# DifferentialProbe.net
KiCad netlist of a schematic drawn in Altium Designer
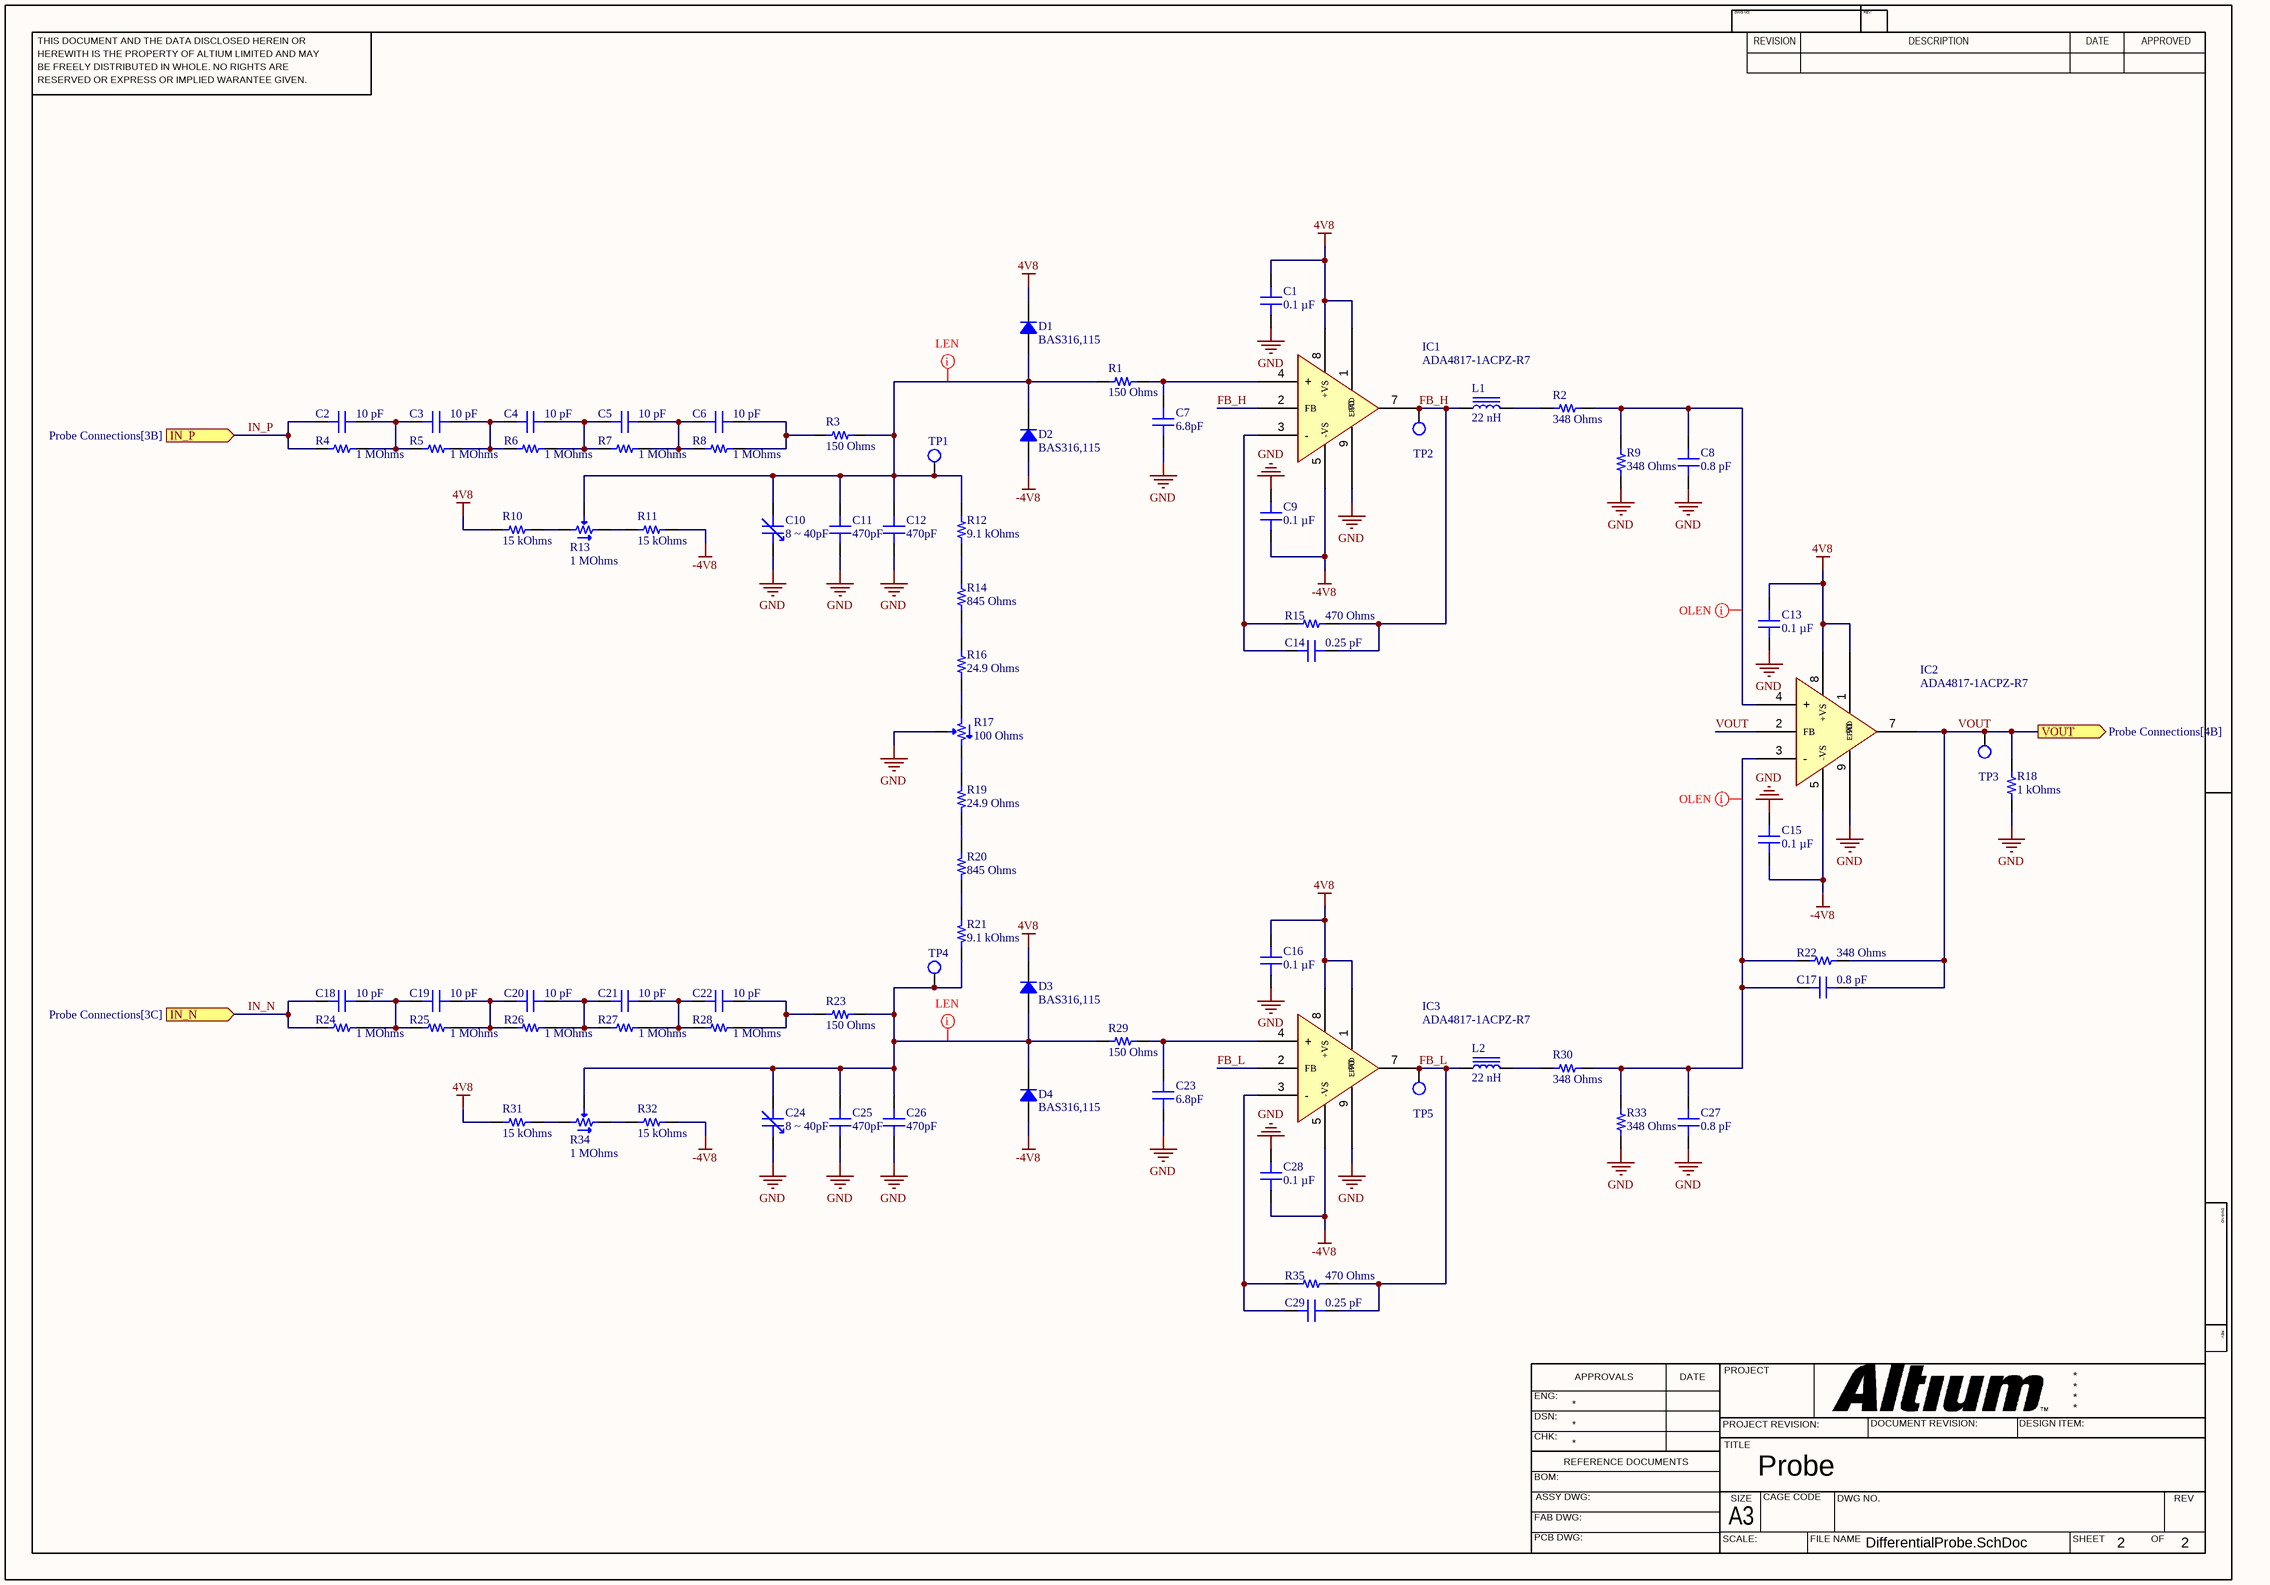
[diagram p0: DifferentialProbe.SchDoc]

(export (version "E")
  (design (tool "Eeschema 10.0.6"))
  (components
    (comp (ref "C1")
      (value "0.1 µF")
      (footprint "CAP 0402_1005")
      (description "CAP CER 0.1UF 10V X7R 0402")
      (fields
        (field (name "PART NUMBER") "0402B104K100CT")
        (field (name "MANUFACTURER") "Walsin Technology Corporation")
      )
      (libsource (lib "altiumlibrary.com") (part "Capacitor"))
    )
    (comp (ref "C2")
      (value "10 pF")
      (footprint "CAP 1206_3216 - 0.8MM")
      (description "CAP CER 10PF 500V C0G/NPO 1206")
      (fields (field (name "PART NUMBER") "CC1206JRNPOBBN100") (field (name "MANUFACTURER") "Yageo"))
      (libsource (lib "altiumlibrary.com") (part "Capacitor"))
    )
    (comp (ref "C3")
      (value "10 pF")
      (footprint "CAP 1206_3216 - 0.8MM")
      (description "CAP CER 10PF 500V C0G/NPO 1206")
      (fields (field (name "PART NUMBER") "CC1206JRNPOBBN100") (field (name "MANUFACTURER") "Yageo"))
      (libsource (lib "altiumlibrary.com") (part "Capacitor"))
    )
    (comp (ref "C4")
      (value "10 pF")
      (footprint "CAP 1206_3216 - 0.8MM")
      (description "CAP CER 10PF 500V C0G/NPO 1206")
      (fields (field (name "PART NUMBER") "CC1206JRNPOBBN100") (field (name "MANUFACTURER") "Yageo"))
      (libsource (lib "altiumlibrary.com") (part "Capacitor"))
    )
    (comp (ref "C5")
      (value "10 pF")
      (footprint "CAP 1206_3216 - 0.8MM")
      (description "CAP CER 10PF 500V C0G/NPO 1206")
      (fields (field (name "PART NUMBER") "CC1206JRNPOBBN100") (field (name "MANUFACTURER") "Yageo"))
      (libsource (lib "altiumlibrary.com") (part "Capacitor"))
    )
    (comp (ref "C6")
      (value "10 pF")
      (footprint "CAP 1206_3216 - 0.8MM")
      (description "CAP CER 10PF 500V C0G/NPO 1206")
      (fields (field (name "PART NUMBER") "CC1206JRNPOBBN100") (field (name "MANUFACTURER") "Yageo"))
      (libsource (lib "altiumlibrary.com") (part "Capacitor"))
    )
    (comp (ref "C7")
      (value "6.8pF")
      (footprint "CAP 0402_1005")
      (description "CAP CER 6.8PF 50V NP0 0402")
      (fields (field (name "PART NUMBER") "04025U6R8BAT2A") (field (name "MANUFACTURER") "AVX Corporation"))
      (libsource (lib "altiumlibrary.com") (part "Capacitor"))
    )
    (comp (ref "C8")
      (value "0.8 pF")
      (footprint "CAP 0402_1005")
      (description "CAP CER 0.8PF 50V C0G/NP0 0402")
      (fields (field (name "PART NUMBER") "CBR04C808C5GAC") (field (name "MANUFACTURER") "KEMET"))
      (libsource (lib "altiumlibrary.com") (part "Capacitor"))
    )
    (comp (ref "C9")
      (value "0.1 µF")
      (footprint "CAP 0402_1005")
      (description "CAP CER 0.1UF 10V X7R 0402")
      (fields
        (field (name "PART NUMBER") "0402B104K100CT")
        (field (name "MANUFACTURER") "Walsin Technology Corporation")
      )
      (libsource (lib "altiumlibrary.com") (part "Capacitor"))
    )
    (comp (ref "C10")
      (value "JZ400")
      (footprint "KNOWLES JZ")
      (description "CAP TRIMMER 8-40PF 125V SMD")
      (fields
        (field (name "CAPACITANCE RANGE") "8 ~ 40pF")
        (field (name "MANUFACTURER") "Knowles Voltronics")
      )
      (libsource (lib "altiumlibrary.com") (part "TRIMMER CAPACITOR"))
    )
    (comp (ref "C11")
      (value "470pF")
      (footprint "CAP 0402_1005")
      (description "CAP CER 470PF 50V C0G/NP0 0402")
      (fields (field (name "PART NUMBER") "04025A471JAT2A") (field (name "MANUFACTURER") "AVX Corporation"))
      (libsource (lib "altiumlibrary.com") (part "Capacitor"))
    )
    (comp (ref "C12")
      (value "470pF")
      (footprint "CAP 0402_1005")
      (description "CAP CER 470PF 50V C0G/NP0 0402")
      (fields (field (name "PART NUMBER") "04025A471JAT2A") (field (name "MANUFACTURER") "AVX Corporation"))
      (libsource (lib "altiumlibrary.com") (part "Capacitor"))
    )
    (comp (ref "C13")
      (value "0.1 µF")
      (footprint "CAP 0402_1005")
      (description "CAP CER 0.1UF 10V X7R 0402")
      (fields
        (field (name "PART NUMBER") "0402B104K100CT")
        (field (name "MANUFACTURER") "Walsin Technology Corporation")
      )
      (libsource (lib "altiumlibrary.com") (part "Capacitor"))
    )
    (comp (ref "C14")
      (value "0.25 pF")
      (footprint "CAP 0402_1005")
      (description "CAP CER 0.25PF 50V C0G/NP0 0402")
      (fields
        (field (name "PART NUMBER") "GCQ1555C1HR25BB01D")
        (field (name "MANUFACTURER") "Murata Electronics")
      )
      (libsource (lib "altiumlibrary.com") (part "Capacitor"))
    )
    (comp (ref "C15")
      (value "0.1 µF")
      (footprint "CAP 0402_1005")
      (description "CAP CER 0.1UF 10V X7R 0402")
      (fields
        (field (name "PART NUMBER") "0402B104K100CT")
        (field (name "MANUFACTURER") "Walsin Technology Corporation")
      )
      (libsource (lib "altiumlibrary.com") (part "Capacitor"))
    )
    (comp (ref "C16")
      (value "0.1 µF")
      (footprint "CAP 0402_1005")
      (description "CAP CER 0.1UF 10V X7R 0402")
      (fields
        (field (name "PART NUMBER") "0402B104K100CT")
        (field (name "MANUFACTURER") "Walsin Technology Corporation")
      )
      (libsource (lib "altiumlibrary.com") (part "Capacitor"))
    )
    (comp (ref "C17")
      (value "0.8 pF")
      (footprint "CAP 0402_1005")
      (description "CAP CER 0.8PF 50V C0G/NPO 0402")
      (fields (field (name "PART NUMBER") "CC0402BRNPO9BNR80") (field (name "MANUFACTURER") "Yageo"))
      (libsource (lib "altiumlibrary.com") (part "Capacitor"))
    )
    (comp (ref "C18")
      (value "10 pF")
      (footprint "CAP 1206_3216 - 0.8MM")
      (description "CAP CER 10PF 500V C0G/NPO 1206")
      (fields (field (name "PART NUMBER") "CC1206JRNPOBBN100") (field (name "MANUFACTURER") "Yageo"))
      (libsource (lib "altiumlibrary.com") (part "Capacitor"))
    )
    (comp (ref "C19")
      (value "10 pF")
      (footprint "CAP 1206_3216 - 0.8MM")
      (description "CAP CER 10PF 500V C0G/NPO 1206")
      (fields (field (name "PART NUMBER") "CC1206JRNPOBBN100") (field (name "MANUFACTURER") "Yageo"))
      (libsource (lib "altiumlibrary.com") (part "Capacitor"))
    )
    (comp (ref "C20")
      (value "10 pF")
      (footprint "CAP 1206_3216 - 0.8MM")
      (description "CAP CER 10PF 500V C0G/NPO 1206")
      (fields (field (name "PART NUMBER") "CC1206JRNPOBBN100") (field (name "MANUFACTURER") "Yageo"))
      (libsource (lib "altiumlibrary.com") (part "Capacitor"))
    )
    (comp (ref "C21")
      (value "10 pF")
      (footprint "CAP 1206_3216 - 0.8MM")
      (description "CAP CER 10PF 500V C0G/NPO 1206")
      (fields (field (name "PART NUMBER") "CC1206JRNPOBBN100") (field (name "MANUFACTURER") "Yageo"))
      (libsource (lib "altiumlibrary.com") (part "Capacitor"))
    )
    (comp (ref "C22")
      (value "10 pF")
      (footprint "CAP 1206_3216 - 0.8MM")
      (description "CAP CER 10PF 500V C0G/NPO 1206")
      (fields (field (name "PART NUMBER") "CC1206JRNPOBBN100") (field (name "MANUFACTURER") "Yageo"))
      (libsource (lib "altiumlibrary.com") (part "Capacitor"))
    )
    (comp (ref "C23")
      (value "6.8pF")
      (footprint "CAP 0402_1005")
      (description "CAP CER 6.8PF 50V NP0 0402")
      (fields (field (name "PART NUMBER") "04025U6R8BAT2A") (field (name "MANUFACTURER") "AVX Corporation"))
      (libsource (lib "altiumlibrary.com") (part "Capacitor"))
    )
    (comp (ref "C24")
      (value "JZ400")
      (footprint "KNOWLES JZ")
      (description "CAP TRIMMER 8-40PF 125V SMD")
      (fields
        (field (name "CAPACITANCE RANGE") "8 ~ 40pF")
        (field (name "MANUFACTURER") "Knowles Voltronics")
      )
      (libsource (lib "altiumlibrary.com") (part "TRIMMER CAPACITOR"))
    )
    (comp (ref "C25")
      (value "470pF")
      (footprint "CAP 0402_1005")
      (description "CAP CER 470PF 50V C0G/NP0 0402")
      (fields (field (name "PART NUMBER") "04025A471JAT2A") (field (name "MANUFACTURER") "AVX Corporation"))
      (libsource (lib "altiumlibrary.com") (part "Capacitor"))
    )
    (comp (ref "C26")
      (value "470pF")
      (footprint "CAP 0402_1005")
      (description "CAP CER 470PF 50V C0G/NP0 0402")
      (fields (field (name "PART NUMBER") "04025A471JAT2A") (field (name "MANUFACTURER") "AVX Corporation"))
      (libsource (lib "altiumlibrary.com") (part "Capacitor"))
    )
    (comp (ref "C27")
      (value "0.8 pF")
      (footprint "CAP 0402_1005")
      (description "CAP CER 0.8PF 50V C0G/NP0 0402")
      (fields (field (name "PART NUMBER") "CBR04C808C5GAC") (field (name "MANUFACTURER") "KEMET"))
      (libsource (lib "altiumlibrary.com") (part "Capacitor"))
    )
    (comp (ref "C28")
      (value "0.1 µF")
      (footprint "CAP 0402_1005")
      (description "CAP CER 0.1UF 10V X7R 0402")
      (fields
        (field (name "PART NUMBER") "0402B104K100CT")
        (field (name "MANUFACTURER") "Walsin Technology Corporation")
      )
      (libsource (lib "altiumlibrary.com") (part "Capacitor"))
    )
    (comp (ref "C29")
      (value "0.25 pF")
      (footprint "CAP 0402_1005")
      (description "CAP CER 0.25PF 50V C0G/NP0 0402")
      (fields
        (field (name "PART NUMBER") "GCQ1555C1HR25BB01D")
        (field (name "MANUFACTURER") "Murata Electronics")
      )
      (libsource (lib "altiumlibrary.com") (part "Capacitor"))
    )
    (comp (ref "D1")
      (value "BAS316,115")
      (footprint "SOD323")
      (description "DIODE GEN PURP 100V 250MA SOD323")
      (fields (field (name "MANUFACTURER") "Nexperia USA Inc."))
      (libsource (lib "altiumlibrary.com") (part "Diode"))
    )
    (comp (ref "D2")
      (value "BAS316,115")
      (footprint "SOD323")
      (description "DIODE GEN PURP 100V 250MA SOD323")
      (fields (field (name "MANUFACTURER") "Nexperia USA Inc."))
      (libsource (lib "altiumlibrary.com") (part "Diode"))
    )
    (comp (ref "D3")
      (value "BAS316,115")
      (footprint "SOD323")
      (description "DIODE GEN PURP 100V 250MA SOD323")
      (fields (field (name "MANUFACTURER") "Nexperia USA Inc."))
      (libsource (lib "altiumlibrary.com") (part "Diode"))
    )
    (comp (ref "D4")
      (value "BAS316,115")
      (footprint "SOD323")
      (description "DIODE GEN PURP 100V 250MA SOD323")
      (fields (field (name "MANUFACTURER") "Nexperia USA Inc."))
      (libsource (lib "altiumlibrary.com") (part "Diode"))
    )
    (comp (ref "IC1")
      (value "ADA4817-1ACPZ-R7")
      (footprint "AD LFCSP-8 3x3MM CP-8-5")
      (description "IC OPAMP VFB 1 CIRCUIT 8LFCSP")
      (fields (field (name "MANUFACTURER") "Analog Devices Inc."))
      (libsource (lib "altiumlibrary.com") (part "ANALOG DEV ADA4817-1 LFCSP"))
    )
    (comp (ref "IC2")
      (value "ADA4817-1ACPZ-R7")
      (footprint "AD LFCSP-8 3x3MM CP-8-5")
      (description "IC OPAMP VFB 1 CIRCUIT 8LFCSP")
      (fields (field (name "MANUFACTURER") "Analog Devices Inc."))
      (libsource (lib "altiumlibrary.com") (part "ANALOG DEV ADA4817-1 LFCSP"))
    )
    (comp (ref "IC3")
      (value "ADA4817-1ACPZ-R7")
      (footprint "AD LFCSP-8 3x3MM CP-8-5")
      (description "IC OPAMP VFB 1 CIRCUIT 8LFCSP")
      (fields (field (name "MANUFACTURER") "Analog Devices Inc."))
      (libsource (lib "altiumlibrary.com") (part "ANALOG DEV ADA4817-1 LFCSP"))
    )
    (comp (ref "L1")
      (value "22 nH")
      (footprint "IND 0402_1005 RF WW")
      (description "FIXED IND 22NH 780MA 202MOHM SMD")
      (fields
        (field (name "PART NUMBER") "LQW15AN22NG80D")
        (field (name "MANUFACTURER") "Murata Electronics")
      )
      (libsource (lib "altiumlibrary.com") (part "Inductor"))
    )
    (comp (ref "L2")
      (value "22 nH")
      (footprint "IND 0402_1005 RF WW")
      (description "FIXED IND 22NH 780MA 202MOHM SMD")
      (fields
        (field (name "PART NUMBER") "LQW15AN22NG80D")
        (field (name "MANUFACTURER") "Murata Electronics")
      )
      (libsource (lib "altiumlibrary.com") (part "Inductor"))
    )
    (comp (ref "R1")
      (value "150 Ohms")
      (footprint "RES 0402_1005")
      (description "RES SMD 150 OHM 0.1% 1/16W 0402")
      (fields (field (name "PART NUMBER") "RG1005P-151-B-T5") (field (name "MANUFACTURER") "Susumu"))
      (libsource (lib "altiumlibrary.com") (part "Resistor"))
    )
    (comp (ref "R2")
      (value "348 Ohms")
      (footprint "RES 0402_1005")
      (description "RES SMD 348 OHM 0.1% 1/16W 0402")
      (fields (field (name "PART NUMBER") "RT0402BRD07348RL") (field (name "MANUFACTURER") "Yageo"))
      (libsource (lib "altiumlibrary.com") (part "Resistor"))
    )
    (comp (ref "R3")
      (value "150 Ohms")
      (footprint "RES 0402_1005")
      (description "RES SMD 150 OHM 0.1% 1/16W 0402")
      (fields (field (name "PART NUMBER") "RG1005P-151-B-T5") (field (name "MANUFACTURER") "Susumu"))
      (libsource (lib "altiumlibrary.com") (part "Resistor"))
    )
    (comp (ref "R4")
      (value "1 MOhms")
      (footprint "RES 1206_3216")
      (description "RES 1M OHM 0.1% 1/8W 1206")
      (fields
        (field (name "PART NUMBER") "RNCS1206BKE1M00")
        (field (name "MANUFACTURER") "Stackpole Electronics Inc")
      )
      (libsource (lib "altiumlibrary.com") (part "Resistor"))
    )
    (comp (ref "R5")
      (value "1 MOhms")
      (footprint "RES 1206_3216")
      (description "RES 1M OHM 0.1% 1/8W 1206")
      (fields
        (field (name "PART NUMBER") "RNCS1206BKE1M00")
        (field (name "MANUFACTURER") "Stackpole Electronics Inc")
      )
      (libsource (lib "altiumlibrary.com") (part "Resistor"))
    )
    (comp (ref "R6")
      (value "1 MOhms")
      (footprint "RES 1206_3216")
      (description "RES 1M OHM 0.1% 1/8W 1206")
      (fields
        (field (name "PART NUMBER") "RNCS1206BKE1M00")
        (field (name "MANUFACTURER") "Stackpole Electronics Inc")
      )
      (libsource (lib "altiumlibrary.com") (part "Resistor"))
    )
    (comp (ref "R7")
      (value "1 MOhms")
      (footprint "RES 1206_3216")
      (description "RES 1M OHM 0.1% 1/8W 1206")
      (fields
        (field (name "PART NUMBER") "RNCS1206BKE1M00")
        (field (name "MANUFACTURER") "Stackpole Electronics Inc")
      )
      (libsource (lib "altiumlibrary.com") (part "Resistor"))
    )
    (comp (ref "R8")
      (value "1 MOhms")
      (footprint "RES 1206_3216")
      (description "RES 1M OHM 0.1% 1/8W 1206")
      (fields
        (field (name "PART NUMBER") "RNCS1206BKE1M00")
        (field (name "MANUFACTURER") "Stackpole Electronics Inc")
      )
      (libsource (lib "altiumlibrary.com") (part "Resistor"))
    )
    (comp (ref "R9")
      (value "348 Ohms")
      (footprint "RES 0402_1005")
      (description "RES SMD 348 OHM 0.1% 1/16W 0402")
      (fields (field (name "PART NUMBER") "RT0402BRD07348RL") (field (name "MANUFACTURER") "Yageo"))
      (libsource (lib "altiumlibrary.com") (part "Resistor"))
    )
    (comp (ref "R10")
      (value "15 kOhms")
      (footprint "RES 0402_1005")
      (description "RES 15K OHM 0.1% 1/16W 0402")
      (fields
        (field (name "PART NUMBER") "RN73R1ETTP1502B25")
        (field (name "MANUFACTURER") "KOA Speer Electronics, Inc.")
      )
      (libsource (lib "altiumlibrary.com") (part "Resistor"))
    )
    (comp (ref "R11")
      (value "15 kOhms")
      (footprint "RES 0402_1005")
      (description "RES 15K OHM 0.1% 1/16W 0402")
      (fields
        (field (name "PART NUMBER") "RN73R1ETTP1502B25")
        (field (name "MANUFACTURER") "KOA Speer Electronics, Inc.")
      )
      (libsource (lib "altiumlibrary.com") (part "Resistor"))
    )
    (comp (ref "R12")
      (value "9.1 kOhms")
      (footprint "RES 0402_1005")
      (description "RES SMD 9.1K OHM 0.1% 1/16W 0402")
      (fields
        (field (name "PART NUMBER") "CPF0402B9K1E1")
        (field (name "MANUFACTURER") "TE Connectivity Passive Product")
      )
      (libsource (lib "altiumlibrary.com") (part "Resistor"))
    )
    (comp (ref "R13")
      (value "1 MOhms")
      (footprint "BOURNS TRIMPOT 3386P-1")
      (description "TRIMMER 1M OHM 0.5W PC PIN TOP")
      (fields (field (name "PART NUMBER") "3386P-1-105LF") (field (name "MANUFACTURER") "Bourns Inc."))
      (libsource (lib "altiumlibrary.com") (part "Potentiometer"))
    )
    (comp (ref "R14")
      (value "845 Ohms")
      (footprint "RES 0402_1005")
      (description "RES SMD 845 OHM 0.1% 1/16W 0402")
      (fields
        (field (name "PART NUMBER") "ERA-2AEB8450X")
        (field (name "MANUFACTURER") "Panasonic Electronic Components")
      )
      (libsource (lib "altiumlibrary.com") (part "Resistor"))
    )
    (comp (ref "R15")
      (value "470 Ohms")
      (footprint "RES 0402_1005")
      (description "RES SMD 470 OHM 0.1% 1/16W 0402")
      (fields (field (name "PART NUMBER") "RT0402BRD07470RL") (field (name "MANUFACTURER") "Yageo"))
      (libsource (lib "altiumlibrary.com") (part "Resistor"))
    )
    (comp (ref "R16")
      (value "24.9 Ohms")
      (footprint "RES 0402_1005")
      (description "RES SMD 24.9 OHM 0.1% 1/16W 0402")
      (fields (field (name "PART NUMBER") "RT0402BRD0724R9L") (field (name "MANUFACTURER") "Yageo"))
      (libsource (lib "altiumlibrary.com") (part "Resistor"))
    )
    (comp (ref "R17")
      (value "100 Ohms")
      (footprint "BOURNS TRIMPOT 3386P-1")
      (description "TRIMMER 100 OHM 0.5W PC PIN TOP")
      (fields (field (name "PART NUMBER") "3386P-1-101LF") (field (name "MANUFACTURER") "Bourns Inc."))
      (libsource (lib "altiumlibrary.com") (part "Potentiometer"))
    )
    (comp (ref "R18")
      (value "1 kOhms")
      (footprint "RES 0402_1005")
      (description "RES 1K OHM 1% 1/16W 0402")
      (fields
        (field (name "PART NUMBER") "RMCF0402FT1K00")
        (field (name "MANUFACTURER") "Stackpole Electronics Inc")
      )
      (libsource (lib "altiumlibrary.com") (part "Resistor"))
    )
    (comp (ref "R19")
      (value "24.9 Ohms")
      (footprint "RES 0402_1005")
      (description "RES SMD 24.9 OHM 0.1% 1/16W 0402")
      (fields (field (name "PART NUMBER") "RT0402BRD0724R9L") (field (name "MANUFACTURER") "Yageo"))
      (libsource (lib "altiumlibrary.com") (part "Resistor"))
    )
    (comp (ref "R20")
      (value "845 Ohms")
      (footprint "RES 0402_1005")
      (description "RES SMD 845 OHM 0.1% 1/16W 0402")
      (fields
        (field (name "PART NUMBER") "ERA-2AEB8450X")
        (field (name "MANUFACTURER") "Panasonic Electronic Components")
      )
      (libsource (lib "altiumlibrary.com") (part "Resistor"))
    )
    (comp (ref "R21")
      (value "9.1 kOhms")
      (footprint "RES 0402_1005")
      (description "RES SMD 9.1K OHM 0.1% 1/16W 0402")
      (fields
        (field (name "PART NUMBER") "CPF0402B9K1E1")
        (field (name "MANUFACTURER") "TE Connectivity Passive Product")
      )
      (libsource (lib "altiumlibrary.com") (part "Resistor"))
    )
    (comp (ref "R22")
      (value "348 Ohms")
      (footprint "RES 0402_1005")
      (description "RES SMD 348 OHM 0.1% 1/16W 0402")
      (fields (field (name "PART NUMBER") "RT0402BRD07348RL") (field (name "MANUFACTURER") "Yageo"))
      (libsource (lib "altiumlibrary.com") (part "Resistor"))
    )
    (comp (ref "R23")
      (value "150 Ohms")
      (footprint "RES 0402_1005")
      (description "RES SMD 150 OHM 0.1% 1/16W 0402")
      (fields (field (name "PART NUMBER") "RG1005P-151-B-T5") (field (name "MANUFACTURER") "Susumu"))
      (libsource (lib "altiumlibrary.com") (part "Resistor"))
    )
    (comp (ref "R24")
      (value "1 MOhms")
      (footprint "RES 1206_3216")
      (description "RES 1M OHM 0.1% 1/8W 1206")
      (fields
        (field (name "PART NUMBER") "RNCS1206BKE1M00")
        (field (name "MANUFACTURER") "Stackpole Electronics Inc")
      )
      (libsource (lib "altiumlibrary.com") (part "Resistor"))
    )
    (comp (ref "R25")
      (value "1 MOhms")
      (footprint "RES 1206_3216")
      (description "RES 1M OHM 0.1% 1/8W 1206")
      (fields
        (field (name "PART NUMBER") "RNCS1206BKE1M00")
        (field (name "MANUFACTURER") "Stackpole Electronics Inc")
      )
      (libsource (lib "altiumlibrary.com") (part "Resistor"))
    )
    (comp (ref "R26")
      (value "1 MOhms")
      (footprint "RES 1206_3216")
      (description "RES 1M OHM 0.1% 1/8W 1206")
      (fields
        (field (name "PART NUMBER") "RNCS1206BKE1M00")
        (field (name "MANUFACTURER") "Stackpole Electronics Inc")
      )
      (libsource (lib "altiumlibrary.com") (part "Resistor"))
    )
    (comp (ref "R27")
      (value "1 MOhms")
      (footprint "RES 1206_3216")
      (description "RES 1M OHM 0.1% 1/8W 1206")
      (fields
        (field (name "PART NUMBER") "RNCS1206BKE1M00")
        (field (name "MANUFACTURER") "Stackpole Electronics Inc")
      )
      (libsource (lib "altiumlibrary.com") (part "Resistor"))
    )
    (comp (ref "R28")
      (value "1 MOhms")
      (footprint "RES 1206_3216")
      (description "RES 1M OHM 0.1% 1/8W 1206")
      (fields
        (field (name "PART NUMBER") "RNCS1206BKE1M00")
        (field (name "MANUFACTURER") "Stackpole Electronics Inc")
      )
      (libsource (lib "altiumlibrary.com") (part "Resistor"))
    )
    (comp (ref "R29")
      (value "150 Ohms")
      (footprint "RES 0402_1005")
      (description "RES SMD 150 OHM 0.1% 1/16W 0402")
      (fields (field (name "PART NUMBER") "RG1005P-151-B-T5") (field (name "MANUFACTURER") "Susumu"))
      (libsource (lib "altiumlibrary.com") (part "Resistor"))
    )
    (comp (ref "R30")
      (value "348 Ohms")
      (footprint "RES 0402_1005")
      (description "RES SMD 348 OHM 0.1% 1/16W 0402")
      (fields (field (name "PART NUMBER") "RT0402BRD07348RL") (field (name "MANUFACTURER") "Yageo"))
      (libsource (lib "altiumlibrary.com") (part "Resistor"))
    )
    (comp (ref "R31")
      (value "15 kOhms")
      (footprint "RES 0402_1005")
      (description "RES 15K OHM 0.1% 1/16W 0402")
      (fields
        (field (name "PART NUMBER") "RN73R1ETTP1502B25")
        (field (name "MANUFACTURER") "KOA Speer Electronics, Inc.")
      )
      (libsource (lib "altiumlibrary.com") (part "Resistor"))
    )
    (comp (ref "R32")
      (value "15 kOhms")
      (footprint "RES 0402_1005")
      (description "RES 15K OHM 0.1% 1/16W 0402")
      (fields
        (field (name "PART NUMBER") "RN73R1ETTP1502B25")
        (field (name "MANUFACTURER") "KOA Speer Electronics, Inc.")
      )
      (libsource (lib "altiumlibrary.com") (part "Resistor"))
    )
    (comp (ref "R33")
      (value "348 Ohms")
      (footprint "RES 0402_1005")
      (description "RES SMD 348 OHM 0.1% 1/16W 0402")
      (fields (field (name "PART NUMBER") "RT0402BRD07348RL") (field (name "MANUFACTURER") "Yageo"))
      (libsource (lib "altiumlibrary.com") (part "Resistor"))
    )
    (comp (ref "R34")
      (value "1 MOhms")
      (footprint "BOURNS TRIMPOT 3386P-1")
      (description "TRIMMER 1M OHM 0.5W PC PIN TOP")
      (fields (field (name "PART NUMBER") "3386P-1-105LF") (field (name "MANUFACTURER") "Bourns Inc."))
      (libsource (lib "altiumlibrary.com") (part "Potentiometer"))
    )
    (comp (ref "R35")
      (value "470 Ohms")
      (footprint "RES 0402_1005")
      (description "RES SMD 470 OHM 0.1% 1/16W 0402")
      (fields (field (name "PART NUMBER") "RT0402BRD07470RL") (field (name "MANUFACTURER") "Yageo"))
      (libsource (lib "altiumlibrary.com") (part "Resistor"))
    )
    (comp (ref "TP1")
      (value "Test Point")
      (footprint "TestPoint-1.5mm")
      (libsource (lib "Original Circuit") (part "Test Point"))
    )
    (comp (ref "TP2")
      (value "Test Point")
      (footprint "TestPoint-1.5mm")
      (libsource (lib "Original Circuit") (part "Test Point"))
    )
    (comp (ref "TP3")
      (value "Test Point")
      (footprint "TestPoint-1.5mm")
      (libsource (lib "Original Circuit") (part "Test Point"))
    )
    (comp (ref "TP4")
      (value "Test Point")
      (footprint "TestPoint-1.5mm")
      (libsource (lib "Original Circuit") (part "Test Point"))
    )
    (comp (ref "TP5")
      (value "Test Point")
      (footprint "TestPoint-1.5mm")
      (libsource (lib "Original Circuit") (part "Test Point"))
    )
  )
  (nets
    (net (code "1") (name "-4V8") (class "Default")
      (node (ref "C15") (pin "1") (pinfunction "1_1") (pintype "passive"))
      (node (ref "C28") (pin "1") (pinfunction "1_1") (pintype "passive"))
      (node (ref "C9") (pin "1") (pinfunction "1_1") (pintype "passive"))
      (node (ref "D2") (pin "1") (pinfunction "1_1") (pintype "passive"))
      (node (ref "D4") (pin "1") (pinfunction "1_1") (pintype "passive"))
      (node (ref "IC1") (pin "5") (pinfunction "-VS_5") (pintype "passive"))
      (node (ref "IC2") (pin "5") (pinfunction "-VS_5") (pintype "passive"))
      (node (ref "IC3") (pin "5") (pinfunction "-VS_5") (pintype "passive"))
      (node (ref "R11") (pin "2") (pinfunction "2_2") (pintype "passive"))
      (node (ref "R32") (pin "2") (pinfunction "2_2") (pintype "passive"))
    )
    (net (code "2") (name "/FB_H") (class "Default")
      (node (ref "C14") (pin "2") (pinfunction "2_2") (pintype "passive"))
      (node (ref "IC1") (pin "2") (pinfunction "FB_2") (pintype "passive"))
      (node (ref "IC1") (pin "7") (pinfunction "OUT_7") (pintype "passive"))
      (node (ref "L1") (pin "1") (pinfunction "1_1") (pintype "passive"))
      (node (ref "R15") (pin "2") (pinfunction "2_2") (pintype "passive"))
      (node (ref "TP2") (pin "1") (pinfunction "TP_1") (pintype "passive"))
    )
    (net (code "3") (name "/FB_L") (class "Default")
      (node (ref "C29") (pin "2") (pinfunction "2_2") (pintype "passive"))
      (node (ref "IC3") (pin "2") (pinfunction "FB_2") (pintype "passive"))
      (node (ref "IC3") (pin "7") (pinfunction "OUT_7") (pintype "passive"))
      (node (ref "L2") (pin "1") (pinfunction "1_1") (pintype "passive"))
      (node (ref "R35") (pin "2") (pinfunction "2_2") (pintype "passive"))
      (node (ref "TP5") (pin "1") (pinfunction "TP_1") (pintype "passive"))
    )
    (net (code "4") (name "/IN_N") (class "Default")
      (node (ref "C18") (pin "1") (pinfunction "1_1") (pintype "passive"))
      (node (ref "R24") (pin "1") (pinfunction "1_1") (pintype "passive"))
    )
    (net (code "5") (name "/IN_P") (class "Default")
      (node (ref "C2") (pin "1") (pinfunction "1_1") (pintype "passive"))
      (node (ref "R4") (pin "1") (pinfunction "1_1") (pintype "passive"))
    )
    (net (code "6") (name "/VOUT") (class "Default")
      (node (ref "C17") (pin "2") (pinfunction "2_2") (pintype "passive"))
      (node (ref "IC2") (pin "2") (pinfunction "FB_2") (pintype "passive"))
      (node (ref "IC2") (pin "7") (pinfunction "OUT_7") (pintype "passive"))
      (node (ref "R18") (pin "2") (pinfunction "2_2") (pintype "passive"))
      (node (ref "R22") (pin "2") (pinfunction "2_2") (pintype "passive"))
      (node (ref "TP3") (pin "1") (pinfunction "TP_1") (pintype "passive"))
    )
    (net (code "7") (name "4V8") (class "Default")
      (node (ref "C1") (pin "2") (pinfunction "2_2") (pintype "passive"))
      (node (ref "C13") (pin "2") (pinfunction "2_2") (pintype "passive"))
      (node (ref "C16") (pin "2") (pinfunction "2_2") (pintype "passive"))
      (node (ref "D1") (pin "2") (pinfunction "2_2") (pintype "passive"))
      (node (ref "D3") (pin "2") (pinfunction "2_2") (pintype "passive"))
      (node (ref "IC1") (pin "1") (pinfunction "~{PD}_1") (pintype "passive"))
      (node (ref "IC1") (pin "8") (pinfunction "+VS_8") (pintype "passive"))
      (node (ref "IC2") (pin "1") (pinfunction "~{PD}_1") (pintype "passive"))
      (node (ref "IC2") (pin "8") (pinfunction "+VS_8") (pintype "passive"))
      (node (ref "IC3") (pin "1") (pinfunction "~{PD}_1") (pintype "passive"))
      (node (ref "IC3") (pin "8") (pinfunction "+VS_8") (pintype "passive"))
      (node (ref "R10") (pin "1") (pinfunction "1_1") (pintype "passive"))
      (node (ref "R31") (pin "1") (pinfunction "1_1") (pintype "passive"))
    )
    (net (code "8") (name "GND") (class "Default")
      (node (ref "C1") (pin "1") (pinfunction "1_1") (pintype "passive"))
      (node (ref "C10") (pin "2") (pinfunction "2_2") (pintype "passive"))
      (node (ref "C11") (pin "1") (pinfunction "1_1") (pintype "passive"))
      (node (ref "C12") (pin "1") (pinfunction "1_1") (pintype "passive"))
      (node (ref "C13") (pin "1") (pinfunction "1_1") (pintype "passive"))
      (node (ref "C15") (pin "2") (pinfunction "2_2") (pintype "passive"))
      (node (ref "C16") (pin "1") (pinfunction "1_1") (pintype "passive"))
      (node (ref "C23") (pin "1") (pinfunction "1_1") (pintype "passive"))
      (node (ref "C24") (pin "2") (pinfunction "2_2") (pintype "passive"))
      (node (ref "C25") (pin "1") (pinfunction "1_1") (pintype "passive"))
      (node (ref "C26") (pin "1") (pinfunction "1_1") (pintype "passive"))
      (node (ref "C27") (pin "2") (pinfunction "2_2") (pintype "passive"))
      (node (ref "C28") (pin "2") (pinfunction "2_2") (pintype "passive"))
      (node (ref "C7") (pin "1") (pinfunction "1_1") (pintype "passive"))
      (node (ref "C8") (pin "2") (pinfunction "2_2") (pintype "passive"))
      (node (ref "C9") (pin "2") (pinfunction "2_2") (pintype "passive"))
      (node (ref "IC1") (pin "9") (pinfunction "EPAD_9") (pintype "passive"))
      (node (ref "IC2") (pin "9") (pinfunction "EPAD_9") (pintype "passive"))
      (node (ref "IC3") (pin "9") (pinfunction "EPAD_9") (pintype "passive"))
      (node (ref "R17") (pin "2") (pinfunction "2_2") (pintype "passive"))
      (node (ref "R18") (pin "1") (pinfunction "1_1") (pintype "passive"))
      (node (ref "R33") (pin "2") (pinfunction "2_2") (pintype "passive"))
      (node (ref "R9") (pin "2") (pinfunction "2_2") (pintype "passive"))
    )
    (net (code "9") (name "Net-(C2-Pad2)") (class "Default")
      (node (ref "C2") (pin "2") (pinfunction "2_2") (pintype "passive"))
      (node (ref "C3") (pin "1") (pinfunction "1_1") (pintype "passive"))
      (node (ref "R4") (pin "2") (pinfunction "2_2") (pintype "passive"))
      (node (ref "R5") (pin "1") (pinfunction "1_1") (pintype "passive"))
    )
    (net (code "10") (name "Net-(C3-Pad2)") (class "Default")
      (node (ref "C3") (pin "2") (pinfunction "2_2") (pintype "passive"))
      (node (ref "C4") (pin "1") (pinfunction "1_1") (pintype "passive"))
      (node (ref "R5") (pin "2") (pinfunction "2_2") (pintype "passive"))
      (node (ref "R6") (pin "1") (pinfunction "1_1") (pintype "passive"))
    )
    (net (code "11") (name "Net-(C4-Pad2)") (class "Default")
      (node (ref "C4") (pin "2") (pinfunction "2_2") (pintype "passive"))
      (node (ref "C5") (pin "1") (pinfunction "1_1") (pintype "passive"))
      (node (ref "R6") (pin "2") (pinfunction "2_2") (pintype "passive"))
      (node (ref "R7") (pin "1") (pinfunction "1_1") (pintype "passive"))
    )
    (net (code "12") (name "Net-(C5-Pad2)") (class "Default")
      (node (ref "C5") (pin "2") (pinfunction "2_2") (pintype "passive"))
      (node (ref "C6") (pin "1") (pinfunction "1_1") (pintype "passive"))
      (node (ref "R7") (pin "2") (pinfunction "2_2") (pintype "passive"))
      (node (ref "R8") (pin "1") (pinfunction "1_1") (pintype "passive"))
    )
    (net (code "13") (name "Net-(C6-Pad2)") (class "Default")
      (node (ref "C6") (pin "2") (pinfunction "2_2") (pintype "passive"))
      (node (ref "R3") (pin "1") (pinfunction "1_1") (pintype "passive"))
      (node (ref "R8") (pin "2") (pinfunction "2_2") (pintype "passive"))
    )
    (net (code "14") (name "Net-(C18-Pad2)") (class "Default")
      (node (ref "C18") (pin "2") (pinfunction "2_2") (pintype "passive"))
      (node (ref "C19") (pin "1") (pinfunction "1_1") (pintype "passive"))
      (node (ref "R24") (pin "2") (pinfunction "2_2") (pintype "passive"))
      (node (ref "R25") (pin "1") (pinfunction "1_1") (pintype "passive"))
    )
    (net (code "15") (name "Net-(C19-Pad2)") (class "Default")
      (node (ref "C19") (pin "2") (pinfunction "2_2") (pintype "passive"))
      (node (ref "C20") (pin "1") (pinfunction "1_1") (pintype "passive"))
      (node (ref "R25") (pin "2") (pinfunction "2_2") (pintype "passive"))
      (node (ref "R26") (pin "1") (pinfunction "1_1") (pintype "passive"))
    )
    (net (code "16") (name "Net-(C20-Pad2)") (class "Default")
      (node (ref "C20") (pin "2") (pinfunction "2_2") (pintype "passive"))
      (node (ref "C21") (pin "1") (pinfunction "1_1") (pintype "passive"))
      (node (ref "R26") (pin "2") (pinfunction "2_2") (pintype "passive"))
      (node (ref "R27") (pin "1") (pinfunction "1_1") (pintype "passive"))
    )
    (net (code "17") (name "Net-(C21-Pad2)") (class "Default")
      (node (ref "C21") (pin "2") (pinfunction "2_2") (pintype "passive"))
      (node (ref "C22") (pin "1") (pinfunction "1_1") (pintype "passive"))
      (node (ref "R27") (pin "2") (pinfunction "2_2") (pintype "passive"))
      (node (ref "R28") (pin "1") (pinfunction "1_1") (pintype "passive"))
    )
    (net (code "18") (name "Net-(C22-Pad2)") (class "Default")
      (node (ref "C22") (pin "2") (pinfunction "2_2") (pintype "passive"))
      (node (ref "R23") (pin "1") (pinfunction "1_1") (pintype "passive"))
      (node (ref "R28") (pin "2") (pinfunction "2_2") (pintype "passive"))
    )
    (net (code "19") (name "Net-(IC1-+)") (class "Default")
      (node (ref "C7") (pin "2") (pinfunction "2_2") (pintype "passive"))
      (node (ref "IC1") (pin "4") (pinfunction "+_4") (pintype "passive"))
      (node (ref "R1") (pin "2") (pinfunction "2_2") (pintype "passive"))
    )
    (net (code "20") (name "Net-(IC1--)") (class "Default")
      (node (ref "C14") (pin "1") (pinfunction "1_1") (pintype "passive"))
      (node (ref "IC1") (pin "3") (pinfunction "-_3") (pintype "passive"))
      (node (ref "R15") (pin "1") (pinfunction "1_1") (pintype "passive"))
    )
    (net (code "21") (name "Net-(IC2-+)") (class "Default")
      (node (ref "C8") (pin "1") (pinfunction "1_1") (pintype "passive"))
      (node (ref "IC2") (pin "4") (pinfunction "+_4") (pintype "passive"))
      (node (ref "R2") (pin "2") (pinfunction "2_2") (pintype "passive"))
      (node (ref "R9") (pin "1") (pinfunction "1_1") (pintype "passive"))
    )
    (net (code "22") (name "Net-(IC2--)") (class "Default")
      (node (ref "C17") (pin "1") (pinfunction "1_1") (pintype "passive"))
      (node (ref "C27") (pin "1") (pinfunction "1_1") (pintype "passive"))
      (node (ref "IC2") (pin "3") (pinfunction "-_3") (pintype "passive"))
      (node (ref "R22") (pin "1") (pinfunction "1_1") (pintype "passive"))
      (node (ref "R30") (pin "2") (pinfunction "2_2") (pintype "passive"))
      (node (ref "R33") (pin "1") (pinfunction "1_1") (pintype "passive"))
    )
    (net (code "23") (name "Net-(IC3-+)") (class "Default")
      (node (ref "C23") (pin "2") (pinfunction "2_2") (pintype "passive"))
      (node (ref "IC3") (pin "4") (pinfunction "+_4") (pintype "passive"))
      (node (ref "R29") (pin "2") (pinfunction "2_2") (pintype "passive"))
    )
    (net (code "24") (name "Net-(IC3--)") (class "Default")
      (node (ref "C29") (pin "1") (pinfunction "1_1") (pintype "passive"))
      (node (ref "IC3") (pin "3") (pinfunction "-_3") (pintype "passive"))
      (node (ref "R35") (pin "1") (pinfunction "1_1") (pintype "passive"))
    )
    (net (code "25") (name "Net-(L1-Pad2)") (class "Default")
      (node (ref "L1") (pin "2") (pinfunction "2_2") (pintype "passive"))
      (node (ref "R2") (pin "1") (pinfunction "1_1") (pintype "passive"))
    )
    (net (code "26") (name "Net-(L2-Pad2)") (class "Default")
      (node (ref "L2") (pin "2") (pinfunction "2_2") (pintype "passive"))
      (node (ref "R30") (pin "1") (pinfunction "1_1") (pintype "passive"))
    )
    (net (code "27") (name "Net-(R10-Pad2)") (class "Default")
      (node (ref "R10") (pin "2") (pinfunction "2_2") (pintype "passive"))
      (node (ref "R13") (pin "1") (pinfunction "1_1") (pintype "passive"))
    )
    (net (code "28") (name "Net-(R11-Pad1)") (class "Default")
      (node (ref "R11") (pin "1") (pinfunction "1_1") (pintype "passive"))
      (node (ref "R13") (pin "3") (pinfunction "3_3") (pintype "passive"))
    )
    (net (code "29") (name "Net-(R12-Pad1)") (class "Default")
      (node (ref "R12") (pin "1") (pinfunction "1_1") (pintype "passive"))
      (node (ref "R14") (pin "2") (pinfunction "2_2") (pintype "passive"))
    )
    (net (code "30") (name "Net-(R14-Pad1)") (class "Default")
      (node (ref "R14") (pin "1") (pinfunction "1_1") (pintype "passive"))
      (node (ref "R16") (pin "2") (pinfunction "2_2") (pintype "passive"))
    )
    (net (code "31") (name "Net-(R16-Pad1)") (class "Default")
      (node (ref "R16") (pin "1") (pinfunction "1_1") (pintype "passive"))
      (node (ref "R17") (pin "1") (pinfunction "1_1") (pintype "passive"))
    )
    (net (code "32") (name "Net-(R17-Pad3)") (class "Default")
      (node (ref "R17") (pin "3") (pinfunction "3_3") (pintype "passive"))
      (node (ref "R19") (pin "1") (pinfunction "1_1") (pintype "passive"))
    )
    (net (code "33") (name "Net-(R19-Pad2)") (class "Default")
      (node (ref "R19") (pin "2") (pinfunction "2_2") (pintype "passive"))
      (node (ref "R20") (pin "1") (pinfunction "1_1") (pintype "passive"))
    )
    (net (code "34") (name "Net-(R20-Pad2)") (class "Default")
      (node (ref "R20") (pin "2") (pinfunction "2_2") (pintype "passive"))
      (node (ref "R21") (pin "1") (pinfunction "1_1") (pintype "passive"))
    )
    (net (code "35") (name "Net-(R31-Pad2)") (class "Default")
      (node (ref "R31") (pin "2") (pinfunction "2_2") (pintype "passive"))
      (node (ref "R34") (pin "1") (pinfunction "1_1") (pintype "passive"))
    )
    (net (code "36") (name "Net-(R32-Pad1)") (class "Default")
      (node (ref "R32") (pin "1") (pinfunction "1_1") (pintype "passive"))
      (node (ref "R34") (pin "3") (pinfunction "3_3") (pintype "passive"))
    )
    (net (code "37") (name "Net-(TP1-TP)") (class "Default")
      (node (ref "C10") (pin "1") (pinfunction "1_1") (pintype "passive"))
      (node (ref "C11") (pin "2") (pinfunction "2_2") (pintype "passive"))
      (node (ref "C12") (pin "2") (pinfunction "2_2") (pintype "passive"))
      (node (ref "D1") (pin "1") (pinfunction "1_1") (pintype "passive"))
      (node (ref "D2") (pin "2") (pinfunction "2_2") (pintype "passive"))
      (node (ref "R1") (pin "1") (pinfunction "1_1") (pintype "passive"))
      (node (ref "R12") (pin "2") (pinfunction "2_2") (pintype "passive"))
      (node (ref "R13") (pin "2") (pinfunction "2_2") (pintype "passive"))
      (node (ref "R3") (pin "2") (pinfunction "2_2") (pintype "passive"))
      (node (ref "TP1") (pin "1") (pinfunction "TP_1") (pintype "passive"))
    )
    (net (code "38") (name "Net-(TP4-TP)") (class "Default")
      (node (ref "C24") (pin "1") (pinfunction "1_1") (pintype "passive"))
      (node (ref "C25") (pin "2") (pinfunction "2_2") (pintype "passive"))
      (node (ref "C26") (pin "2") (pinfunction "2_2") (pintype "passive"))
      (node (ref "D3") (pin "1") (pinfunction "1_1") (pintype "passive"))
      (node (ref "D4") (pin "2") (pinfunction "2_2") (pintype "passive"))
      (node (ref "R21") (pin "2") (pinfunction "2_2") (pintype "passive"))
      (node (ref "R23") (pin "2") (pinfunction "2_2") (pintype "passive"))
      (node (ref "R29") (pin "1") (pinfunction "1_1") (pintype "passive"))
      (node (ref "R34") (pin "2") (pinfunction "2_2") (pintype "passive"))
      (node (ref "TP4") (pin "1") (pinfunction "TP_1") (pintype "passive"))
    )
  )
)
